# k210.net
KiCad netlist of a schematic drawn in Altium Designer
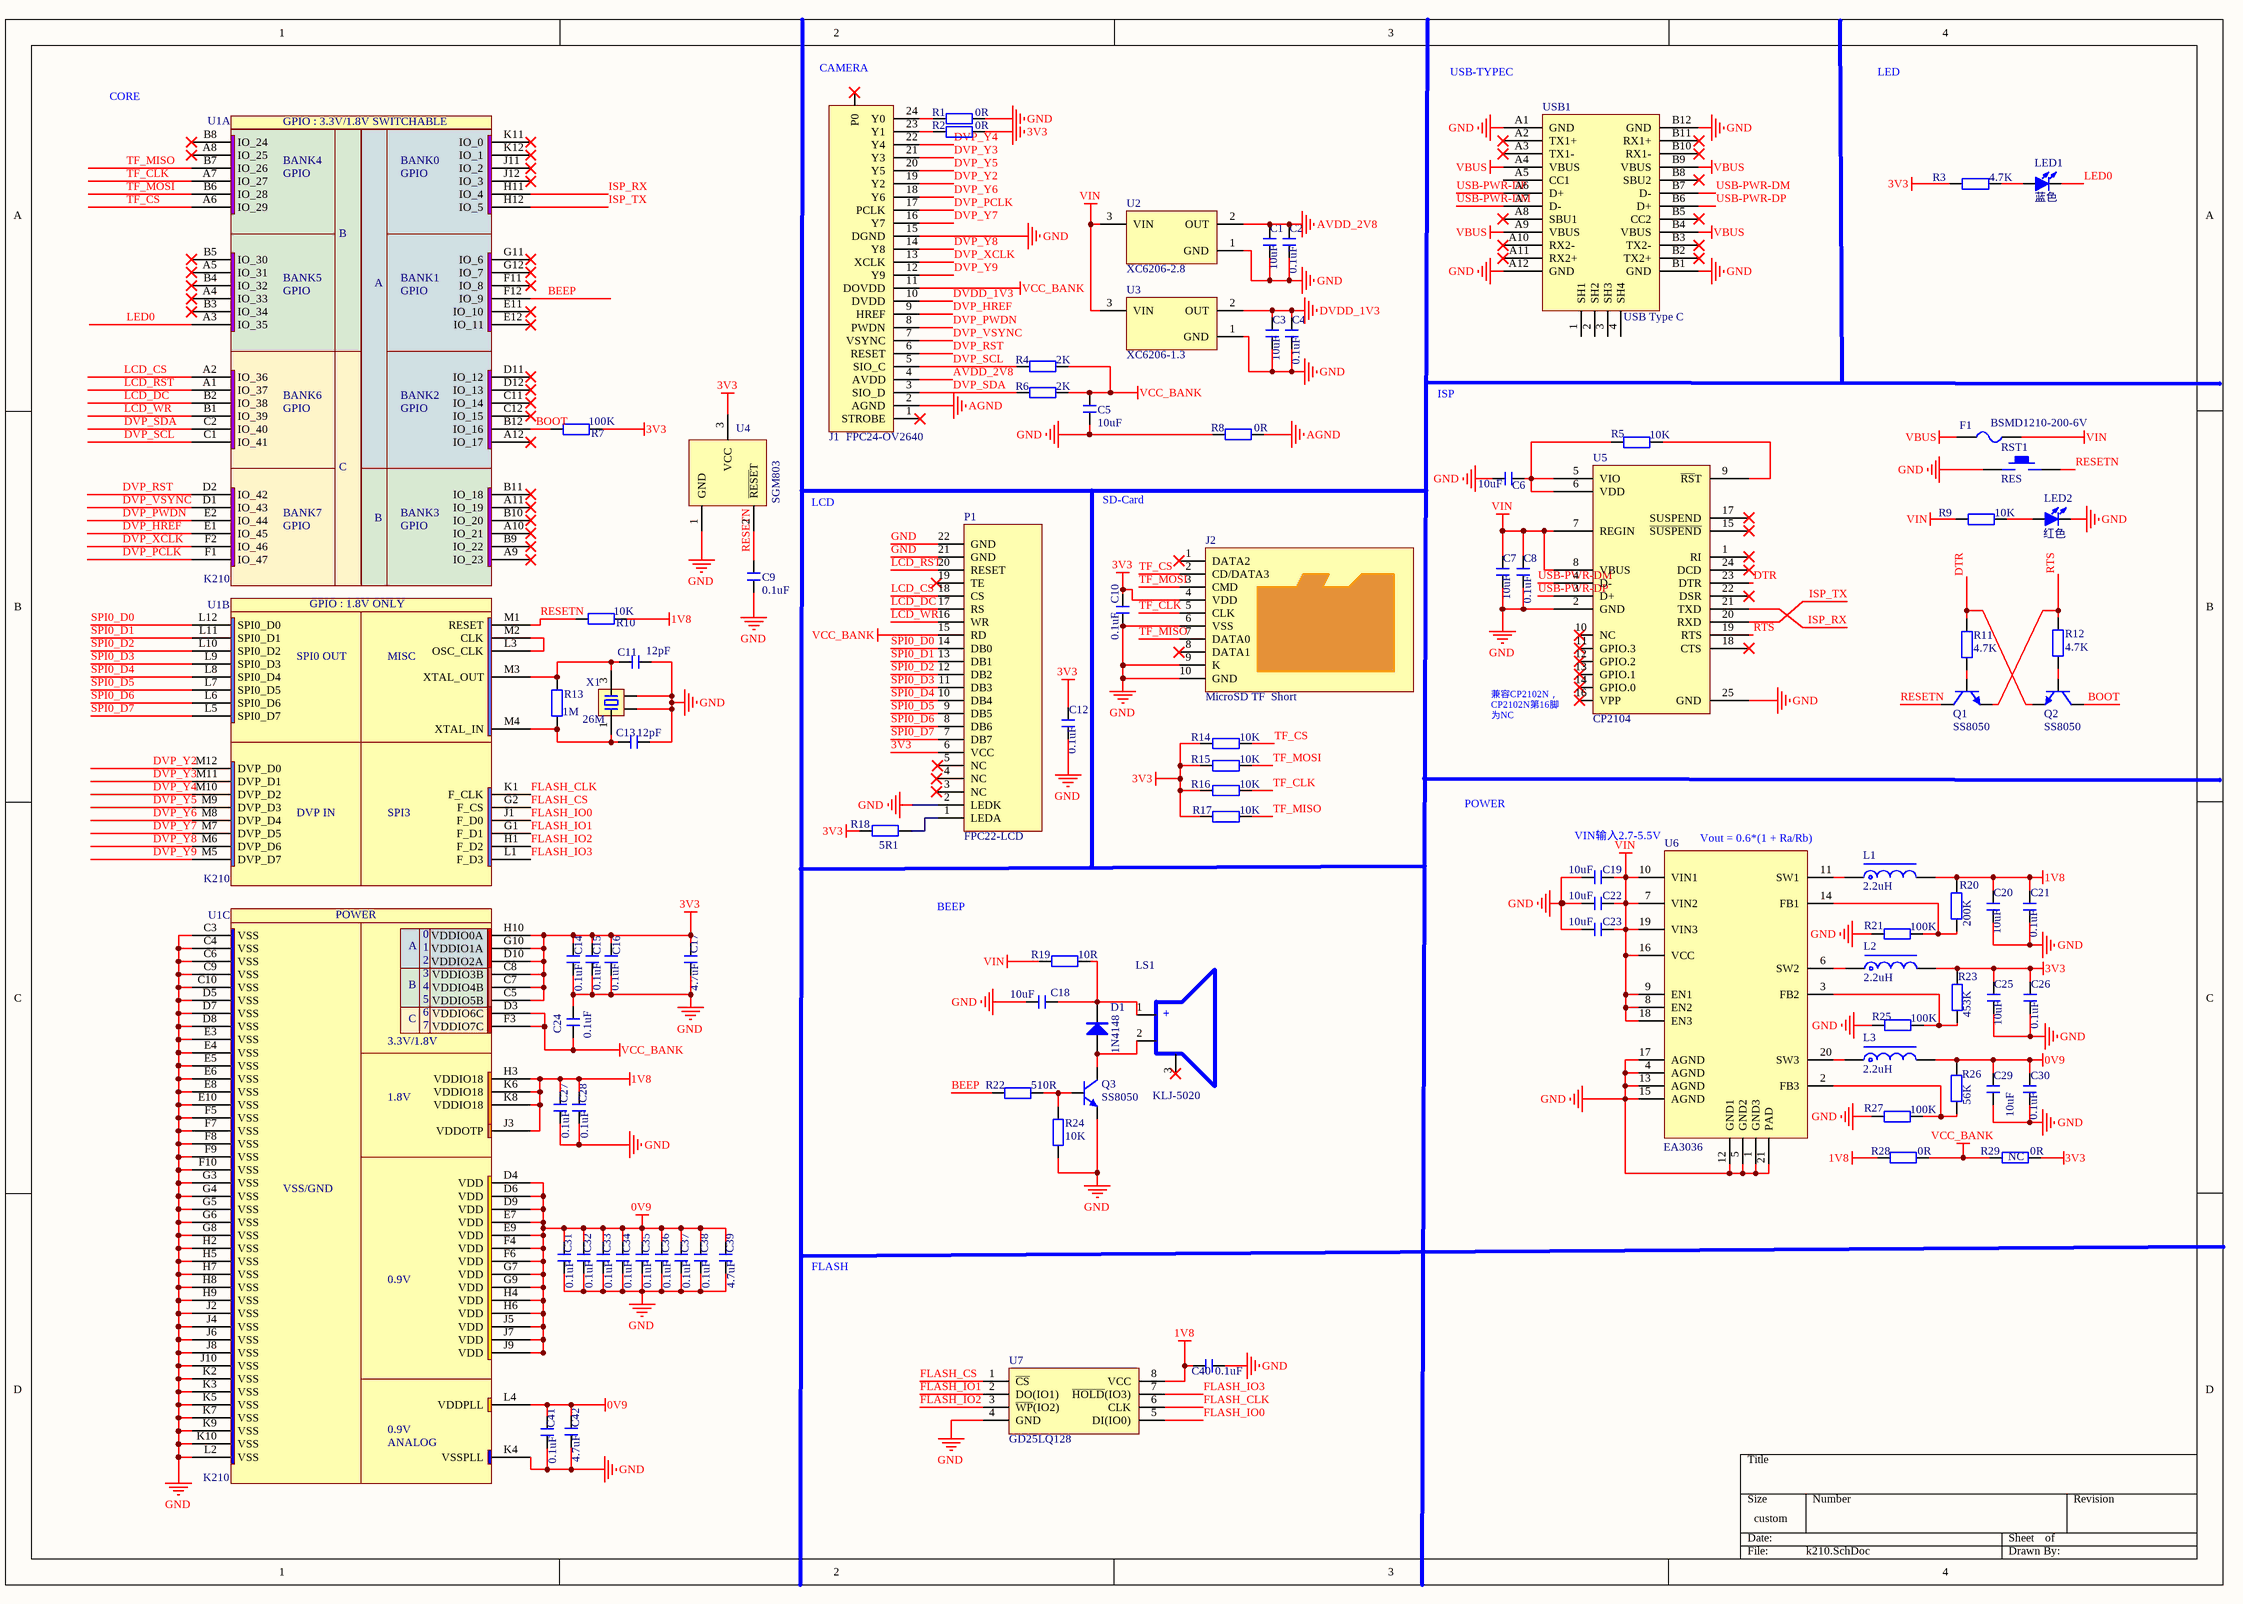
[diagram p0: k210.SchDoc]

(export (version "E")
  (design (tool "Eeschema 10.0.6"))
  (components
    (comp (ref "C1")
      (value "10uF")
      (footprint "C 0402_M")
      (description "贴片电容")
      (libsource (lib "0.1 - 电阻-电容-电感") (part "C"))
    )
    (comp (ref "C2")
      (value "0.1uF")
      (footprint "C 0402_M")
      (description "贴片电容")
      (libsource (lib "0.1 - 电阻-电容-电感") (part "C"))
    )
    (comp (ref "C3")
      (value "10uF")
      (footprint "C 0402_M")
      (description "贴片电容")
      (libsource (lib "0.1 - 电阻-电容-电感") (part "C"))
    )
    (comp (ref "C4")
      (value "0.1uF")
      (footprint "C 0402_M")
      (description "贴片电容")
      (libsource (lib "0.1 - 电阻-电容-电感") (part "C"))
    )
    (comp (ref "C5")
      (value "10uF")
      (footprint "C 0402_M")
      (description "贴片电容")
      (libsource (lib "0.1 - 电阻-电容-电感") (part "C"))
    )
    (comp (ref "C6")
      (value "10uF")
      (footprint "C 0402_M")
      (description "贴片电容")
      (libsource (lib "0.1 - 电阻-电容-电感") (part "C"))
    )
    (comp (ref "C7")
      (value "10uF")
      (footprint "C 0402_M")
      (description "贴片电容")
      (libsource (lib "0.1 - 电阻-电容-电感") (part "C"))
    )
    (comp (ref "C8")
      (value "0.1uF")
      (footprint "C 0402_M")
      (description "贴片电容")
      (libsource (lib "0.1 - 电阻-电容-电感") (part "C"))
    )
    (comp (ref "C9")
      (value "0.1uF")
      (footprint "C 0402_M")
      (description "贴片电容")
      (libsource (lib "0.1 - 电阻-电容-电感") (part "C"))
    )
    (comp (ref "C10")
      (value "0.1uF")
      (footprint "C 0402_M")
      (description "贴片电容")
      (libsource (lib "0.1 - 电阻-电容-电感") (part "C"))
    )
    (comp (ref "C11")
      (value "12pF")
      (footprint "C 0402_M")
      (description "贴片电容")
      (libsource (lib "0.1 - 电阻-电容-电感") (part "C"))
    )
    (comp (ref "C12")
      (value "0.1uF")
      (footprint "C 0402_M")
      (description "贴片电容")
      (libsource (lib "0.1 - 电阻-电容-电感") (part "C"))
    )
    (comp (ref "C13")
      (value "12pF")
      (footprint "C 0402_M")
      (description "贴片电容")
      (libsource (lib "0.1 - 电阻-电容-电感") (part "C"))
    )
    (comp (ref "C14")
      (value "0.1uF")
      (footprint "C 0402_M")
      (description "贴片电容")
      (libsource (lib "0.1 - 电阻-电容-电感") (part "C"))
    )
    (comp (ref "C15")
      (value "0.1uF")
      (footprint "C 0402_M")
      (description "贴片电容")
      (libsource (lib "0.1 - 电阻-电容-电感") (part "C"))
    )
    (comp (ref "C16")
      (value "0.1uF")
      (footprint "C 0402_M")
      (description "贴片电容")
      (libsource (lib "0.1 - 电阻-电容-电感") (part "C"))
    )
    (comp (ref "C17")
      (value "4.7uF")
      (footprint "C 0402_M")
      (description "贴片电容")
      (libsource (lib "0.1 - 电阻-电容-电感") (part "C"))
    )
    (comp (ref "C18")
      (value "10uF")
      (footprint "C 0402_M")
      (description "贴片电容")
      (libsource (lib "0.1 - 电阻-电容-电感") (part "C"))
    )
    (comp (ref "C19")
      (value "10uF")
      (footprint "C 0402_M")
      (description "贴片电容")
      (libsource (lib "0.1 - 电阻-电容-电感") (part "C"))
    )
    (comp (ref "C20")
      (value "10uF")
      (footprint "C 0402_M")
      (description "贴片电容")
      (libsource (lib "0.1 - 电阻-电容-电感") (part "C"))
    )
    (comp (ref "C21")
      (value "0.1uF")
      (footprint "C 0402_M")
      (description "贴片电容")
      (libsource (lib "0.1 - 电阻-电容-电感") (part "C"))
    )
    (comp (ref "C22")
      (value "10uF")
      (footprint "C 0402_M")
      (description "贴片电容")
      (libsource (lib "0.1 - 电阻-电容-电感") (part "C"))
    )
    (comp (ref "C23")
      (value "10uF")
      (footprint "C 0402_M")
      (description "贴片电容")
      (libsource (lib "0.1 - 电阻-电容-电感") (part "C"))
    )
    (comp (ref "C24")
      (value "0.1uF")
      (footprint "C 0402_M")
      (description "贴片电容")
      (libsource (lib "0.1 - 电阻-电容-电感") (part "C"))
    )
    (comp (ref "C25")
      (value "10uF")
      (footprint "C 0402_M")
      (description "贴片电容")
      (libsource (lib "0.1 - 电阻-电容-电感") (part "C"))
    )
    (comp (ref "C26")
      (value "0.1uF")
      (footprint "C 0402_M")
      (description "贴片电容")
      (libsource (lib "0.1 - 电阻-电容-电感") (part "C"))
    )
    (comp (ref "C27")
      (value "0.1uF")
      (footprint "C 0402_M")
      (description "贴片电容")
      (libsource (lib "0.1 - 电阻-电容-电感") (part "C"))
    )
    (comp (ref "C28")
      (value "0.1uF")
      (footprint "C 0402_M")
      (description "贴片电容")
      (libsource (lib "0.1 - 电阻-电容-电感") (part "C"))
    )
    (comp (ref "C29")
      (value "10uF")
      (footprint "C 0402_M")
      (description "贴片电容")
      (libsource (lib "0.1 - 电阻-电容-电感") (part "C"))
    )
    (comp (ref "C30")
      (value "0.1uF")
      (footprint "C 0402_M")
      (description "贴片电容")
      (libsource (lib "0.1 - 电阻-电容-电感") (part "C"))
    )
    (comp (ref "C31")
      (value "0.1uF")
      (footprint "C 0402_M")
      (description "贴片电容")
      (libsource (lib "0.1 - 电阻-电容-电感") (part "C"))
    )
    (comp (ref "C32")
      (value "0.1uF")
      (footprint "C 0402_M")
      (description "贴片电容")
      (libsource (lib "0.1 - 电阻-电容-电感") (part "C"))
    )
    (comp (ref "C33")
      (value "0.1uF")
      (footprint "C 0402_M")
      (description "贴片电容")
      (libsource (lib "0.1 - 电阻-电容-电感") (part "C"))
    )
    (comp (ref "C34")
      (value "0.1uF")
      (footprint "C 0402_M")
      (description "贴片电容")
      (libsource (lib "0.1 - 电阻-电容-电感") (part "C"))
    )
    (comp (ref "C35")
      (value "0.1uF")
      (footprint "C 0402_M")
      (description "贴片电容")
      (libsource (lib "0.1 - 电阻-电容-电感") (part "C"))
    )
    (comp (ref "C36")
      (value "0.1uF")
      (footprint "C 0402_M")
      (description "贴片电容")
      (libsource (lib "0.1 - 电阻-电容-电感") (part "C"))
    )
    (comp (ref "C37")
      (value "0.1uF")
      (footprint "C 0402_M")
      (description "贴片电容")
      (libsource (lib "0.1 - 电阻-电容-电感") (part "C"))
    )
    (comp (ref "C38")
      (value "0.1uF")
      (footprint "C 0402_M")
      (description "贴片电容")
      (libsource (lib "0.1 - 电阻-电容-电感") (part "C"))
    )
    (comp (ref "C39")
      (value "4.7uF")
      (footprint "C 0402_M")
      (description "贴片电容")
      (libsource (lib "0.1 - 电阻-电容-电感") (part "C"))
    )
    (comp (ref "C40")
      (value "0.1uF")
      (footprint "C 0402_M")
      (description "贴片电容")
      (libsource (lib "0.1 - 电阻-电容-电感") (part "C"))
    )
    (comp (ref "C41")
      (value "0.1uF")
      (footprint "C 0402_M")
      (description "贴片电容")
      (libsource (lib "0.1 - 电阻-电容-电感") (part "C"))
    )
    (comp (ref "C42")
      (value "4.7uF")
      (footprint "C 0402_M")
      (description "贴片电容")
      (libsource (lib "0.1 - 电阻-电容-电感") (part "C"))
    )
    (comp (ref "D1")
      (value "1N4148")
      (footprint "SOD-323")
      (description "开关二极管")
      (libsource (lib "0.2 -  二极管-整流桥") (part "1N4148"))
    )
    (comp (ref "F1")
      (value "BSMD1210-200-6V")
      (footprint "FU 1210")
      (description "贴片保险丝")
      (libsource (lib "2.0 - 保险丝-晶振-光耦") (part "FU"))
    )
    (comp (ref "J1")
      (value "FPC24-OV2640")
      (footprint "FPC0.5 2H-WS-24P")
      (description "Header, 24-Pin")
      (fields (field (name "PUBLISHER") "Altium Limited"))
      (libsource (lib "Vowstar_MCU") (part "OV5640"))
    )
    (comp (ref "J2")
      (value "MicroSD TF  Short")
      (footprint "TF-SOCKET - short")
      (description "TF卡座")
      (libsource (lib "0.8 - 网口-音频插座") (part "TF_Card"))
    )
    (comp (ref "L1")
      (value "2.2uH")
      (footprint "NR2520")
      (description "NR磁胶电感")
      (libsource (lib "0.1 - 电阻-电容-电感") (part "L-NR"))
    )
    (comp (ref "L2")
      (value "2.2uH")
      (footprint "NR2520")
      (description "NR磁胶电感")
      (libsource (lib "0.1 - 电阻-电容-电感") (part "L-NR"))
    )
    (comp (ref "L3")
      (value "2.2uH")
      (footprint "NR2520")
      (description "NR磁胶电感")
      (libsource (lib "0.1 - 电阻-电容-电感") (part "L-NR"))
    )
    (comp (ref "LED1")
      (value "蓝色")
      (footprint "LED 0805G")
      (description "贴片LED")
      (libsource (lib "0.3 - LED发光二极管") (part "LED-SMD"))
    )
    (comp (ref "LED2")
      (value "红色")
      (footprint "LED 0805G")
      (description "贴片LED")
      (libsource (lib "0.3 - LED发光二极管") (part "LED-SMD"))
    )
    (comp (ref "LS1")
      (value "KLJ-5020")
      (footprint "BUZ-SMD_4P-L5.0-W5.0-P3.80-TL")
      (description "蜂鸣器")
      (libsource (lib "mx_pcb_library") (part "KLJ-5020"))
    )
    (comp (ref "P1")
      (value "FPC22-LCD")
      (footprint "FPC0.5 2H-WS-22P")
      (libsource (lib "CanMV-K210") (part "FPC22_new"))
    )
    (comp (ref "Q1")
      (value "SS8050")
      (footprint "SOT23-3N")
      (description "高频放大-NPN型")
      (libsource (lib "0.4 - 三极管") (part "8050-SMD"))
    )
    (comp (ref "Q2")
      (value "SS8050")
      (footprint "SOT23-3N")
      (description "高频放大-NPN型")
      (libsource (lib "0.4 - 三极管") (part "8050-SMD"))
    )
    (comp (ref "Q3")
      (value "SS8050")
      (footprint "SOT23-3N")
      (description "高频放大-NPN型")
      (libsource (lib "0.4 - 三极管") (part "8050-SMD"))
    )
    (comp (ref "R1")
      (value "0R")
      (footprint "R 0402_M")
      (description "贴片电阻")
      (libsource (lib "0.1 - 电阻-电容-电感") (part "R"))
    )
    (comp (ref "R2")
      (value "0R")
      (footprint "R 0402_M")
      (description "贴片电阻")
      (libsource (lib "0.1 - 电阻-电容-电感") (part "R"))
    )
    (comp (ref "R3")
      (value "4.7K")
      (footprint "R 0402_M")
      (description "贴片电阻")
      (libsource (lib "0.1 - 电阻-电容-电感") (part "R"))
    )
    (comp (ref "R4")
      (value "2K")
      (footprint "R 0402_M")
      (description "贴片电阻")
      (libsource (lib "0.1 - 电阻-电容-电感") (part "R"))
    )
    (comp (ref "R5")
      (value "10K")
      (footprint "R 0402_M")
      (description "贴片电阻")
      (libsource (lib "0.1 - 电阻-电容-电感") (part "R"))
    )
    (comp (ref "R6")
      (value "2K")
      (footprint "R 0402_M")
      (description "贴片电阻")
      (libsource (lib "0.1 - 电阻-电容-电感") (part "R"))
    )
    (comp (ref "R7")
      (value "100K")
      (footprint "R 0402_M")
      (description "贴片电阻")
      (libsource (lib "0.1 - 电阻-电容-电感") (part "R"))
    )
    (comp (ref "R8")
      (value "0R")
      (footprint "R 0402_M")
      (description "贴片电阻")
      (libsource (lib "0.1 - 电阻-电容-电感") (part "R"))
    )
    (comp (ref "R9")
      (value "10K")
      (footprint "R 0402_M")
      (description "贴片电阻")
      (libsource (lib "0.1 - 电阻-电容-电感") (part "R"))
    )
    (comp (ref "R10")
      (value "10K")
      (footprint "R 0402_M")
      (description "贴片电阻")
      (libsource (lib "0.1 - 电阻-电容-电感") (part "R"))
    )
    (comp (ref "R11")
      (value "4.7K")
      (footprint "R 0402_M")
      (description "贴片电阻")
      (libsource (lib "0.1 - 电阻-电容-电感") (part "R"))
    )
    (comp (ref "R12")
      (value "4.7K")
      (footprint "R 0402_M")
      (description "贴片电阻")
      (libsource (lib "0.1 - 电阻-电容-电感") (part "R"))
    )
    (comp (ref "R13")
      (value "1M")
      (footprint "R 0402_M")
      (description "贴片电阻")
      (libsource (lib "0.1 - 电阻-电容-电感") (part "R"))
    )
    (comp (ref "R14")
      (value "10K")
      (footprint "R 0402_M")
      (description "贴片电阻")
      (libsource (lib "0.1 - 电阻-电容-电感") (part "R"))
    )
    (comp (ref "R15")
      (value "10K")
      (footprint "R 0402_M")
      (description "贴片电阻")
      (libsource (lib "0.1 - 电阻-电容-电感") (part "R"))
    )
    (comp (ref "R16")
      (value "10K")
      (footprint "R 0402_M")
      (description "贴片电阻")
      (libsource (lib "0.1 - 电阻-电容-电感") (part "R"))
    )
    (comp (ref "R17")
      (value "10K")
      (footprint "R 0402_M")
      (description "贴片电阻")
      (libsource (lib "0.1 - 电阻-电容-电感") (part "R"))
    )
    (comp (ref "R18")
      (value "5R1")
      (footprint "R 0402_M")
      (description "贴片电阻")
      (libsource (lib "0.1 - 电阻-电容-电感") (part "R"))
    )
    (comp (ref "R19")
      (value "10R")
      (footprint "R 0402_M")
      (description "贴片电阻")
      (libsource (lib "0.1 - 电阻-电容-电感") (part "R"))
    )
    (comp (ref "R20")
      (value "200K")
      (footprint "R 0402_M")
      (description "贴片电阻")
      (libsource (lib "0.1 - 电阻-电容-电感") (part "R"))
    )
    (comp (ref "R21")
      (value "100K")
      (footprint "R 0402_M")
      (description "贴片电阻")
      (libsource (lib "0.1 - 电阻-电容-电感") (part "R"))
    )
    (comp (ref "R22")
      (value "510R")
      (footprint "R 0402_M")
      (description "贴片电阻")
      (libsource (lib "0.1 - 电阻-电容-电感") (part "R"))
    )
    (comp (ref "R23")
      (value "453K")
      (footprint "R 0402_M")
      (description "贴片电阻")
      (libsource (lib "0.1 - 电阻-电容-电感") (part "R"))
    )
    (comp (ref "R24")
      (value "10K")
      (footprint "R 0402_M")
      (description "贴片电阻")
      (libsource (lib "0.1 - 电阻-电容-电感") (part "R"))
    )
    (comp (ref "R25")
      (value "100K")
      (footprint "R 0402_M")
      (description "贴片电阻")
      (libsource (lib "0.1 - 电阻-电容-电感") (part "R"))
    )
    (comp (ref "R26")
      (value "56K")
      (footprint "R 0402_M")
      (description "贴片电阻")
      (libsource (lib "0.1 - 电阻-电容-电感") (part "R"))
    )
    (comp (ref "R27")
      (value "100K")
      (footprint "R 0402_M")
      (description "贴片电阻")
      (libsource (lib "0.1 - 电阻-电容-电感") (part "R"))
    )
    (comp (ref "R28")
      (value "0R")
      (footprint "R 0402_M")
      (description "贴片电阻")
      (libsource (lib "0.1 - 电阻-电容-电感") (part "R"))
    )
    (comp (ref "R29")
      (value "0R")
      (footprint "R 0402_M")
      (description "贴片电阻")
      (libsource (lib "0.1 - 电阻-电容-电感") (part "R"))
    )
    (comp (ref "RST1")
      (value "RES")
      (footprint "CanMV-K210:SMD-3.2*4.2")
      (libsource (lib "mx_pcb_library") (part "KEY_M"))
    )
    (comp (ref "U1")
      (value "K210")
      (footprint "BGA144C65P12X12_800X800X95")
      (description "Canaan Kendryte K210 AI SoC")
      (libsource (lib "Vowstar_MCU") (part "K210"))
    )
    (comp (ref "U2")
      (value "XC6206-2.8")
      (footprint "CanMV-K210:SOT23-3N")
      (description "SOT-23,XC6206P332MR,MAX8V,100mA")
      (libsource (lib "1.1 - 电源类芯片") (part "XC6206-3.3"))
    )
    (comp (ref "U3")
      (value "XC6206-1.3")
      (footprint "CanMV-K210:SOT23-3N")
      (description "SOT-23,XC6206P332MR,MAX8V,100mA")
      (libsource (lib "1.1 - 电源类芯片") (part "XC6206-3.3"))
    )
    (comp (ref "U4")
      (value "SGM803")
      (footprint "CanMV-K210:SOT23-3N")
      (libsource (lib "Vowstar_MCU") (part "SGM803"))
    )
    (comp (ref "U5")
      (value "CP2104")
      (footprint "QFN-24_L4.0-W4.0-P0.50-BL-EP2.8")
      (libsource (lib "Vowstar_MCU") (part "CP2104"))
    )
    (comp (ref "U6")
      (value "EA3036")
      (footprint "QFN20_40P300X300X80_HS-21N")
      (libsource (lib "Vowstar_MCU") (part "EA3036"))
    )
    (comp (ref "U7")
      (value "GD25LQ128")
      (footprint "WSON-8_L8.0-W6.10-P1.27-BL-EP")
      (description "WSON-8")
      (libsource (lib "Vowstar_MCU") (part "GD25LQ128"))
    )
    (comp (ref "USB1")
      (value "USB Type C")
      (footprint "Type-C-TOP")
      (libsource (lib "Vowstar_MCU") (part "USB_Type-C"))
    )
    (comp (ref "X1")
      (value "26M")
      (footprint "OSC 3225-4P")
      (description "4脚无源晶振")
      (libsource (lib "2.0 - 保险丝-晶振-光耦") (part "XTAL-4P"))
    )
  )
  (nets
    (net (code "1") (name "/BEEP") (class "Default")
      (node (ref "R22") (pin "1") (pinfunction "1_1") (pintype "passive"))
      (node (ref "U1") (pin "F12") (pinfunction "IO_9_F12") (pintype "passive"))
    )
    (net (code "2") (name "/BOOT") (class "Default")
      (node (ref "Q2") (pin "3") (pinfunction "C_3") (pintype "passive"))
      (node (ref "R7") (pin "1") (pinfunction "1_1") (pintype "passive"))
      (node (ref "U1") (pin "B12") (pinfunction "IO_16_B12") (pintype "passive"))
    )
    (net (code "3") (name "/DTR") (class "Default")
      (node (ref "Q2") (pin "2") (pinfunction "E_2") (pintype "passive"))
      (node (ref "R11") (pin "1") (pinfunction "1_1") (pintype "passive"))
      (node (ref "U5") (pin "23") (pinfunction "DTR_23") (pintype "passive"))
    )
    (net (code "4") (name "/DVP_HREF") (class "Default")
      (node (ref "J1") (pin "9") (pinfunction "HREF_9") (pintype "passive"))
      (node (ref "U1") (pin "E1") (pinfunction "IO_45_E1") (pintype "passive"))
    )
    (net (code "5") (name "/DVP_PCLK") (class "Default")
      (node (ref "J1") (pin "17") (pinfunction "PCLK_17") (pintype "passive"))
      (node (ref "U1") (pin "F1") (pinfunction "IO_47_F1") (pintype "passive"))
    )
    (net (code "6") (name "/DVP_PWDN") (class "Default")
      (node (ref "J1") (pin "8") (pinfunction "PWDN_8") (pintype "passive"))
      (node (ref "U1") (pin "E2") (pinfunction "IO_44_E2") (pintype "passive"))
    )
    (net (code "7") (name "/DVP_RST") (class "Default")
      (node (ref "J1") (pin "6") (pinfunction "RESET_6") (pintype "passive"))
      (node (ref "U1") (pin "D2") (pinfunction "IO_42_D2") (pintype "passive"))
    )
    (net (code "8") (name "/DVP_SCL") (class "Default")
      (node (ref "J1") (pin "5") (pinfunction "SIO_C_5") (pintype "passive"))
      (node (ref "R4") (pin "1") (pinfunction "1_1") (pintype "passive"))
      (node (ref "U1") (pin "C1") (pinfunction "IO_41_C1") (pintype "passive"))
    )
    (net (code "9") (name "/DVP_SDA") (class "Default")
      (node (ref "J1") (pin "3") (pinfunction "SIO_D_3") (pintype "passive"))
      (node (ref "R6") (pin "1") (pinfunction "1_1") (pintype "passive"))
      (node (ref "U1") (pin "C2") (pinfunction "IO_40_C2") (pintype "passive"))
    )
    (net (code "10") (name "/DVP_VSYNC") (class "Default")
      (node (ref "J1") (pin "7") (pinfunction "VSYNC_7") (pintype "passive"))
      (node (ref "U1") (pin "D1") (pinfunction "IO_43_D1") (pintype "passive"))
    )
    (net (code "11") (name "/DVP_XCLK") (class "Default")
      (node (ref "J1") (pin "13") (pinfunction "XCLK_13") (pintype "passive"))
      (node (ref "U1") (pin "F2") (pinfunction "IO_46_F2") (pintype "passive"))
    )
    (net (code "12") (name "/DVP_Y2") (class "Default")
      (node (ref "J1") (pin "19") (pinfunction "Y2_19") (pintype "passive"))
      (node (ref "U1") (pin "M12") (pinfunction "DVP_D0_M12") (pintype "passive"))
    )
    (net (code "13") (name "/DVP_Y3") (class "Default")
      (node (ref "J1") (pin "21") (pinfunction "Y3_21") (pintype "passive"))
      (node (ref "U1") (pin "M11") (pinfunction "DVP_D1_M11") (pintype "passive"))
    )
    (net (code "14") (name "/DVP_Y4") (class "Default")
      (node (ref "J1") (pin "22") (pinfunction "Y4_22") (pintype "passive"))
      (node (ref "U1") (pin "M10") (pinfunction "DVP_D2_M10") (pintype "passive"))
    )
    (net (code "15") (name "/DVP_Y5") (class "Default")
      (node (ref "J1") (pin "20") (pinfunction "Y5_20") (pintype "passive"))
      (node (ref "U1") (pin "M9") (pinfunction "DVP_D3_M9") (pintype "passive"))
    )
    (net (code "16") (name "/DVP_Y6") (class "Default")
      (node (ref "J1") (pin "18") (pinfunction "Y6_18") (pintype "passive"))
      (node (ref "U1") (pin "M8") (pinfunction "DVP_D4_M8") (pintype "passive"))
    )
    (net (code "17") (name "/DVP_Y7") (class "Default")
      (node (ref "J1") (pin "16") (pinfunction "Y7_16") (pintype "passive"))
      (node (ref "U1") (pin "M7") (pinfunction "DVP_D5_M7") (pintype "passive"))
    )
    (net (code "18") (name "/DVP_Y8") (class "Default")
      (node (ref "J1") (pin "14") (pinfunction "Y8_14") (pintype "passive"))
      (node (ref "U1") (pin "M6") (pinfunction "DVP_D6_M6") (pintype "passive"))
    )
    (net (code "19") (name "/DVP_Y9") (class "Default")
      (node (ref "J1") (pin "12") (pinfunction "Y9_12") (pintype "passive"))
      (node (ref "U1") (pin "M5") (pinfunction "DVP_D7_M5") (pintype "passive"))
    )
    (net (code "20") (name "/FLASH_CLK") (class "Default")
      (node (ref "U1") (pin "K1") (pinfunction "F_CLK_K1") (pintype "passive"))
      (node (ref "U7") (pin "6") (pinfunction "CLK_6") (pintype "passive"))
    )
    (net (code "21") (name "/FLASH_CS") (class "Default")
      (node (ref "U1") (pin "G2") (pinfunction "F_CS_G2") (pintype "passive"))
      (node (ref "U7") (pin "1") (pinfunction "~{CS}_1") (pintype "passive"))
    )
    (net (code "22") (name "/FLASH_IO0") (class "Default")
      (node (ref "U1") (pin "J1") (pinfunction "F_D0_J1") (pintype "passive"))
      (node (ref "U7") (pin "5") (pinfunction "DI(IO0)_5") (pintype "passive"))
    )
    (net (code "23") (name "/FLASH_IO1") (class "Default")
      (node (ref "U1") (pin "G1") (pinfunction "F_D1_G1") (pintype "passive"))
      (node (ref "U7") (pin "2") (pinfunction "DO(IO1)_2") (pintype "passive"))
    )
    (net (code "24") (name "/FLASH_IO2") (class "Default")
      (node (ref "U1") (pin "H1") (pinfunction "F_D2_H1") (pintype "passive"))
      (node (ref "U7") (pin "3") (pinfunction "~{WP}(IO2)_3") (pintype "passive"))
    )
    (net (code "25") (name "/FLASH_IO3") (class "Default")
      (node (ref "U1") (pin "L1") (pinfunction "F_D3_L1") (pintype "passive"))
      (node (ref "U7") (pin "7") (pinfunction "~{HOLD}(IO3)_7") (pintype "passive"))
    )
    (net (code "26") (name "/ISP_RX") (class "Default")
      (node (ref "U1") (pin "H11") (pinfunction "IO_4_H11") (pintype "passive"))
      (node (ref "U5") (pin "21") (pinfunction "TXD_21") (pintype "passive"))
    )
    (net (code "27") (name "/ISP_TX") (class "Default")
      (node (ref "U1") (pin "H12") (pinfunction "IO_5_H12") (pintype "passive"))
      (node (ref "U5") (pin "20") (pinfunction "RXD_20") (pintype "passive"))
    )
    (net (code "28") (name "/LCD_CS") (class "Default")
      (node (ref "P1") (pin "18") (pinfunction "CS_18") (pintype "passive"))
      (node (ref "U1") (pin "A2") (pinfunction "IO_36_A2") (pintype "passive"))
    )
    (net (code "29") (name "/LCD_DC") (class "Default")
      (node (ref "P1") (pin "17") (pinfunction "RS_17") (pintype "passive"))
      (node (ref "U1") (pin "B2") (pinfunction "IO_38_B2") (pintype "passive"))
    )
    (net (code "30") (name "/LCD_RST") (class "Default")
      (node (ref "P1") (pin "20") (pinfunction "RESET_20") (pintype "passive"))
      (node (ref "U1") (pin "A1") (pinfunction "IO_37_A1") (pintype "passive"))
    )
    (net (code "31") (name "/LCD_WR") (class "Default")
      (node (ref "P1") (pin "16") (pinfunction "WR_16") (pintype "passive"))
      (node (ref "U1") (pin "B1") (pinfunction "IO_39_B1") (pintype "passive"))
    )
    (net (code "32") (name "/LED0") (class "Default")
      (node (ref "LED1") (pin "2") (pinfunction "K_2") (pintype "passive"))
      (node (ref "U1") (pin "A3") (pinfunction "IO_35_A3") (pintype "passive"))
    )
    (net (code "33") (name "/RESETN") (class "Default")
      (node (ref "C9") (pin "1") (pinfunction "1_1") (pintype "passive"))
      (node (ref "Q1") (pin "3") (pinfunction "C_3") (pintype "passive"))
      (node (ref "R10") (pin "1") (pinfunction "1_1") (pintype "passive"))
      (node (ref "RST1") (pin "2") (pinfunction "2_2") (pintype "passive"))
      (node (ref "U1") (pin "M1") (pinfunction "RESET_M1") (pintype "passive"))
      (node (ref "U4") (pin "2") (pinfunction "~{RESE}T_2") (pintype "passive"))
    )
    (net (code "34") (name "/RTS") (class "Default")
      (node (ref "Q1") (pin "2") (pinfunction "E_2") (pintype "passive"))
      (node (ref "R12") (pin "1") (pinfunction "1_1") (pintype "passive"))
      (node (ref "U5") (pin "19") (pinfunction "RTS_19") (pintype "passive"))
    )
    (net (code "35") (name "/SPI0_D0") (class "Default")
      (node (ref "P1") (pin "14") (pinfunction "DB0_14") (pintype "passive"))
      (node (ref "U1") (pin "L12") (pinfunction "SPI0_D0_L12") (pintype "passive"))
    )
    (net (code "36") (name "/SPI0_D1") (class "Default")
      (node (ref "P1") (pin "13") (pinfunction "DB1_13") (pintype "passive"))
      (node (ref "U1") (pin "L11") (pinfunction "SPI0_D1_L11") (pintype "passive"))
    )
    (net (code "37") (name "/SPI0_D2") (class "Default")
      (node (ref "P1") (pin "12") (pinfunction "DB2_12") (pintype "passive"))
      (node (ref "U1") (pin "L10") (pinfunction "SPI0_D2_L10") (pintype "passive"))
    )
    (net (code "38") (name "/SPI0_D3") (class "Default")
      (node (ref "P1") (pin "11") (pinfunction "DB3_11") (pintype "passive"))
      (node (ref "U1") (pin "L9") (pinfunction "SPI0_D3_L9") (pintype "passive"))
    )
    (net (code "39") (name "/SPI0_D4") (class "Default")
      (node (ref "P1") (pin "10") (pinfunction "DB4_10") (pintype "passive"))
      (node (ref "U1") (pin "L8") (pinfunction "SPI0_D4_L8") (pintype "passive"))
    )
    (net (code "40") (name "/SPI0_D5") (class "Default")
      (node (ref "P1") (pin "9") (pinfunction "DB5_9") (pintype "passive"))
      (node (ref "U1") (pin "L7") (pinfunction "SPI0_D5_L7") (pintype "passive"))
    )
    (net (code "41") (name "/SPI0_D6") (class "Default")
      (node (ref "P1") (pin "8") (pinfunction "DB6_8") (pintype "passive"))
      (node (ref "U1") (pin "L6") (pinfunction "SPI0_D6_L6") (pintype "passive"))
    )
    (net (code "42") (name "/SPI0_D7") (class "Default")
      (node (ref "P1") (pin "7") (pinfunction "DB7_7") (pintype "passive"))
      (node (ref "U1") (pin "L5") (pinfunction "SPI0_D7_L5") (pintype "passive"))
    )
    (net (code "43") (name "/TF_CLK") (class "Default")
      (node (ref "J2") (pin "5") (pinfunction "CLK_5") (pintype "passive"))
      (node (ref "R16") (pin "2") (pinfunction "2_2") (pintype "passive"))
      (node (ref "U1") (pin "A7") (pinfunction "IO_27_A7") (pintype "passive"))
    )
    (net (code "44") (name "/TF_CS") (class "Default")
      (node (ref "J2") (pin "2") (pinfunction "CD/DATA3_2") (pintype "passive"))
      (node (ref "R14") (pin "2") (pinfunction "2_2") (pintype "passive"))
      (node (ref "U1") (pin "A6") (pinfunction "IO_29_A6") (pintype "passive"))
    )
    (net (code "45") (name "/TF_MISO") (class "Default")
      (node (ref "J2") (pin "7") (pinfunction "DATA0_7") (pintype "passive"))
      (node (ref "R17") (pin "2") (pinfunction "2_2") (pintype "passive"))
      (node (ref "U1") (pin "B7") (pinfunction "IO_26_B7") (pintype "passive"))
    )
    (net (code "46") (name "/TF_MOSI") (class "Default")
      (node (ref "J2") (pin "3") (pinfunction "CMD_3") (pintype "passive"))
      (node (ref "R15") (pin "2") (pinfunction "2_2") (pintype "passive"))
      (node (ref "U1") (pin "B6") (pinfunction "IO_28_B6") (pintype "passive"))
    )
    (net (code "47") (name "/USB-PWR-DM") (class "Default")
      (node (ref "U5") (pin "4") (pinfunction "D-_4") (pintype "passive"))
      (node (ref "USB1") (pin "A7") (pinfunction "D-_A7") (pintype "passive"))
      (node (ref "USB1") (pin "B7") (pinfunction "D-_B7") (pintype "passive"))
    )
    (net (code "48") (name "/USB-PWR-DP") (class "Default")
      (node (ref "U5") (pin "3") (pinfunction "D+_3") (pintype "passive"))
      (node (ref "USB1") (pin "A6") (pinfunction "D+_A6") (pintype "passive"))
      (node (ref "USB1") (pin "B6") (pinfunction "D+_B6") (pintype "passive"))
    )
    (net (code "49") (name "0V9") (class "Default")
      (node (ref "C29") (pin "2") (pinfunction "2_2") (pintype "passive"))
      (node (ref "C30") (pin "2") (pinfunction "2_2") (pintype "passive"))
      (node (ref "C31") (pin "1") (pinfunction "1_1") (pintype "passive"))
      (node (ref "C32") (pin "1") (pinfunction "1_1") (pintype "passive"))
      (node (ref "C33") (pin "1") (pinfunction "1_1") (pintype "passive"))
      (node (ref "C34") (pin "1") (pinfunction "1_1") (pintype "passive"))
      (node (ref "C35") (pin "1") (pinfunction "1_1") (pintype "passive"))
      (node (ref "C36") (pin "1") (pinfunction "1_1") (pintype "passive"))
      (node (ref "C37") (pin "1") (pinfunction "1_1") (pintype "passive"))
      (node (ref "C38") (pin "1") (pinfunction "1_1") (pintype "passive"))
      (node (ref "C39") (pin "1") (pinfunction "1_1") (pintype "passive"))
      (node (ref "C41") (pin "1") (pinfunction "1_1") (pintype "passive"))
      (node (ref "C42") (pin "1") (pinfunction "1_1") (pintype "passive"))
      (node (ref "L3") (pin "2") (pinfunction "2_2") (pintype "passive"))
      (node (ref "R26") (pin "2") (pinfunction "2_2") (pintype "passive"))
      (node (ref "U1") (pin "D4") (pinfunction "VDD_D4") (pintype "power_in"))
      (node (ref "U1") (pin "D6") (pinfunction "VDD_D6") (pintype "power_in"))
      (node (ref "U1") (pin "D9") (pinfunction "VDD_D9") (pintype "power_in"))
      (node (ref "U1") (pin "E7") (pinfunction "VDD_E7") (pintype "power_in"))
      (node (ref "U1") (pin "E9") (pinfunction "VDD_E9") (pintype "power_in"))
      (node (ref "U1") (pin "F4") (pinfunction "VDD_F4") (pintype "power_in"))
      (node (ref "U1") (pin "F6") (pinfunction "VDD_F6") (pintype "power_in"))
      (node (ref "U1") (pin "G7") (pinfunction "VDD_G7") (pintype "power_in"))
      (node (ref "U1") (pin "G9") (pinfunction "VDD_G9") (pintype "power_in"))
      (node (ref "U1") (pin "H4") (pinfunction "VDD_H4") (pintype "power_in"))
      (node (ref "U1") (pin "H6") (pinfunction "VDD_H6") (pintype "power_in"))
      (node (ref "U1") (pin "J5") (pinfunction "VDD_J5") (pintype "power_in"))
      (node (ref "U1") (pin "J7") (pinfunction "VDD_J7") (pintype "power_in"))
      (node (ref "U1") (pin "J9") (pinfunction "VDD_J9") (pintype "power_in"))
      (node (ref "U1") (pin "L4") (pinfunction "VDDPLL_L4") (pintype "power_in"))
    )
    (net (code "50") (name "1V8") (class "Default")
      (node (ref "C20") (pin "2") (pinfunction "2_2") (pintype "passive"))
      (node (ref "C21") (pin "2") (pinfunction "2_2") (pintype "passive"))
      (node (ref "C27") (pin "1") (pinfunction "1_1") (pintype "passive"))
      (node (ref "C28") (pin "1") (pinfunction "1_1") (pintype "passive"))
      (node (ref "C40") (pin "2") (pinfunction "2_2") (pintype "passive"))
      (node (ref "L1") (pin "2") (pinfunction "2_2") (pintype "passive"))
      (node (ref "R10") (pin "2") (pinfunction "2_2") (pintype "passive"))
      (node (ref "R20") (pin "2") (pinfunction "2_2") (pintype "passive"))
      (node (ref "R28") (pin "2") (pinfunction "2_2") (pintype "passive"))
      (node (ref "U1") (pin "H3") (pinfunction "VDDIO18_H3") (pintype "power_in"))
      (node (ref "U1") (pin "J3") (pinfunction "VDDOTP_J3") (pintype "power_in"))
      (node (ref "U1") (pin "K6") (pinfunction "VDDIO18_K6") (pintype "power_in"))
      (node (ref "U1") (pin "K8") (pinfunction "VDDIO18_K8") (pintype "power_in"))
      (node (ref "U7") (pin "8") (pinfunction "VCC_8") (pintype "passive"))
    )
    (net (code "51") (name "3V3") (class "Default")
      (node (ref "C10") (pin "1") (pinfunction "1_1") (pintype "passive"))
      (node (ref "C12") (pin "2") (pinfunction "2_2") (pintype "passive"))
      (node (ref "C14") (pin "2") (pinfunction "2_2") (pintype "passive"))
      (node (ref "C15") (pin "2") (pinfunction "2_2") (pintype "passive"))
      (node (ref "C16") (pin "2") (pinfunction "2_2") (pintype "passive"))
      (node (ref "C17") (pin "2") (pinfunction "2_2") (pintype "passive"))
      (node (ref "C25") (pin "2") (pinfunction "2_2") (pintype "passive"))
      (node (ref "C26") (pin "2") (pinfunction "2_2") (pintype "passive"))
      (node (ref "J2") (pin "4") (pinfunction "VDD_4") (pintype "passive"))
      (node (ref "L2") (pin "2") (pinfunction "2_2") (pintype "passive"))
      (node (ref "P1") (pin "6") (pinfunction "VCC_6") (pintype "passive"))
      (node (ref "R14") (pin "1") (pinfunction "1_1") (pintype "passive"))
      (node (ref "R15") (pin "1") (pinfunction "1_1") (pintype "passive"))
      (node (ref "R16") (pin "1") (pinfunction "1_1") (pintype "passive"))
      (node (ref "R17") (pin "1") (pinfunction "1_1") (pintype "passive"))
      (node (ref "R18") (pin "1") (pinfunction "1_1") (pintype "passive"))
      (node (ref "R2") (pin "2") (pinfunction "2_2") (pintype "passive"))
      (node (ref "R23") (pin "2") (pinfunction "2_2") (pintype "passive"))
      (node (ref "R29") (pin "1") (pinfunction "1_1") (pintype "passive"))
      (node (ref "R3") (pin "1") (pinfunction "1_1") (pintype "passive"))
      (node (ref "R7") (pin "2") (pinfunction "2_2") (pintype "passive"))
      (node (ref "U1") (pin "C5") (pinfunction "VDDIO5B_C5") (pintype "power_in"))
      (node (ref "U1") (pin "C7") (pinfunction "VDDIO4B_C7") (pintype "power_in"))
      (node (ref "U1") (pin "C8") (pinfunction "VDDIO3B_C8") (pintype "power_in"))
      (node (ref "U1") (pin "D10") (pinfunction "VDDIO2A_D10") (pintype "power_in"))
      (node (ref "U1") (pin "G10") (pinfunction "VDDIO1A_G10") (pintype "power_in"))
      (node (ref "U1") (pin "H10") (pinfunction "VDDIO0A_H10") (pintype "power_in"))
      (node (ref "U4") (pin "3") (pinfunction "VCC_3") (pintype "passive"))
    )
    (net (code "52") (name "AGND") (class "Default")
      (node (ref "J1") (pin "2") (pinfunction "AGND_2") (pintype "passive"))
      (node (ref "R8") (pin "2") (pinfunction "2_2") (pintype "passive"))
    )
    (net (code "53") (name "AVDD_2V8") (class "Default")
      (node (ref "C1") (pin "2") (pinfunction "2_2") (pintype "passive"))
      (node (ref "C2") (pin "2") (pinfunction "2_2") (pintype "passive"))
      (node (ref "J1") (pin "4") (pinfunction "AVDD_4") (pintype "passive"))
      (node (ref "U2") (pin "2") (pinfunction "OUT_2") (pintype "passive"))
    )
    (net (code "54") (name "DVDD_1V3") (class "Default")
      (node (ref "C3") (pin "2") (pinfunction "2_2") (pintype "passive"))
      (node (ref "C4") (pin "2") (pinfunction "2_2") (pintype "passive"))
      (node (ref "J1") (pin "10") (pinfunction "DVDD_10") (pintype "passive"))
      (node (ref "U3") (pin "2") (pinfunction "OUT_2") (pintype "passive"))
    )
    (net (code "55") (name "GND") (class "Default")
      (node (ref "C1") (pin "1") (pinfunction "1_1") (pintype "passive"))
      (node (ref "C10") (pin "2") (pinfunction "2_2") (pintype "passive"))
      (node (ref "C11") (pin "2") (pinfunction "2_2") (pintype "passive"))
      (node (ref "C12") (pin "1") (pinfunction "1_1") (pintype "passive"))
      (node (ref "C13") (pin "2") (pinfunction "2_2") (pintype "passive"))
      (node (ref "C14") (pin "1") (pinfunction "1_1") (pintype "passive"))
      (node (ref "C15") (pin "1") (pinfunction "1_1") (pintype "passive"))
      (node (ref "C16") (pin "1") (pinfunction "1_1") (pintype "passive"))
      (node (ref "C17") (pin "1") (pinfunction "1_1") (pintype "passive"))
      (node (ref "C18") (pin "1") (pinfunction "1_1") (pintype "passive"))
      (node (ref "C19") (pin "2") (pinfunction "2_2") (pintype "passive"))
      (node (ref "C2") (pin "1") (pinfunction "1_1") (pintype "passive"))
      (node (ref "C20") (pin "1") (pinfunction "1_1") (pintype "passive"))
      (node (ref "C21") (pin "1") (pinfunction "1_1") (pintype "passive"))
      (node (ref "C22") (pin "2") (pinfunction "2_2") (pintype "passive"))
      (node (ref "C23") (pin "2") (pinfunction "2_2") (pintype "passive"))
      (node (ref "C24") (pin "1") (pinfunction "1_1") (pintype "passive"))
      (node (ref "C25") (pin "1") (pinfunction "1_1") (pintype "passive"))
      (node (ref "C26") (pin "1") (pinfunction "1_1") (pintype "passive"))
      (node (ref "C27") (pin "2") (pinfunction "2_2") (pintype "passive"))
      (node (ref "C28") (pin "2") (pinfunction "2_2") (pintype "passive"))
      (node (ref "C29") (pin "1") (pinfunction "1_1") (pintype "passive"))
      (node (ref "C3") (pin "1") (pinfunction "1_1") (pintype "passive"))
      (node (ref "C30") (pin "1") (pinfunction "1_1") (pintype "passive"))
      (node (ref "C31") (pin "2") (pinfunction "2_2") (pintype "passive"))
      (node (ref "C32") (pin "2") (pinfunction "2_2") (pintype "passive"))
      (node (ref "C33") (pin "2") (pinfunction "2_2") (pintype "passive"))
      (node (ref "C34") (pin "2") (pinfunction "2_2") (pintype "passive"))
      (node (ref "C35") (pin "2") (pinfunction "2_2") (pintype "passive"))
      (node (ref "C36") (pin "2") (pinfunction "2_2") (pintype "passive"))
      (node (ref "C37") (pin "2") (pinfunction "2_2") (pintype "passive"))
      (node (ref "C38") (pin "2") (pinfunction "2_2") (pintype "passive"))
      (node (ref "C39") (pin "2") (pinfunction "2_2") (pintype "passive"))
      (node (ref "C4") (pin "1") (pinfunction "1_1") (pintype "passive"))
      (node (ref "C40") (pin "1") (pinfunction "1_1") (pintype "passive"))
      (node (ref "C41") (pin "2") (pinfunction "2_2") (pintype "passive"))
      (node (ref "C42") (pin "2") (pinfunction "2_2") (pintype "passive"))
      (node (ref "C5") (pin "2") (pinfunction "2_2") (pintype "passive"))
      (node (ref "C6") (pin "2") (pinfunction "2_2") (pintype "passive"))
      (node (ref "C7") (pin "1") (pinfunction "1_1") (pintype "passive"))
      (node (ref "C8") (pin "1") (pinfunction "1_1") (pintype "passive"))
      (node (ref "C9") (pin "2") (pinfunction "2_2") (pintype "passive"))
      (node (ref "J1") (pin "15") (pinfunction "DGND_15") (pintype "passive"))
      (node (ref "J2") (pin "10") (pinfunction "GND_10") (pintype "passive"))
      (node (ref "J2") (pin "6") (pinfunction "VSS_6") (pintype "passive"))
      (node (ref "J2") (pin "9") (pinfunction "K_9") (pintype "passive"))
      (node (ref "LED2") (pin "2") (pinfunction "K_2") (pintype "passive"))
      (node (ref "P1") (pin "2") (pinfunction "LEDK_2") (pintype "passive"))
      (node (ref "P1") (pin "21") (pinfunction "GND_21") (pintype "passive"))
      (node (ref "P1") (pin "22") (pinfunction "GND_22") (pintype "passive"))
      (node (ref "Q3") (pin "2") (pinfunction "E_2") (pintype "passive"))
      (node (ref "R1") (pin "2") (pinfunction "2_2") (pintype "passive"))
      (node (ref "R21") (pin "2") (pinfunction "2_2") (pintype "passive"))
      (node (ref "R24") (pin "1") (pinfunction "1_1") (pintype "passive"))
      (node (ref "R25") (pin "2") (pinfunction "2_2") (pintype "passive"))
      (node (ref "R27") (pin "2") (pinfunction "2_2") (pintype "passive"))
      (node (ref "R8") (pin "1") (pinfunction "1_1") (pintype "passive"))
      (node (ref "RST1") (pin "1") (pinfunction "1_1") (pintype "passive"))
      (node (ref "U1") (pin "C10") (pinfunction "VSS_C10") (pintype "power_in"))
      (node (ref "U1") (pin "C3") (pinfunction "VSS_C3") (pintype "power_in"))
      (node (ref "U1") (pin "C4") (pinfunction "VSS_C4") (pintype "power_in"))
      (node (ref "U1") (pin "C6") (pinfunction "VSS_C6") (pintype "power_in"))
      (node (ref "U1") (pin "C9") (pinfunction "VSS_C9") (pintype "power_in"))
      (node (ref "U1") (pin "D5") (pinfunction "VSS_D5") (pintype "power_in"))
      (node (ref "U1") (pin "D7") (pinfunction "VSS_D7") (pintype "power_in"))
      (node (ref "U1") (pin "D8") (pinfunction "VSS_D8") (pintype "power_in"))
      (node (ref "U1") (pin "E10") (pinfunction "VSS_E10") (pintype "power_in"))
      (node (ref "U1") (pin "E3") (pinfunction "VSS_E3") (pintype "power_in"))
      (node (ref "U1") (pin "E4") (pinfunction "VSS_E4") (pintype "power_in"))
      (node (ref "U1") (pin "E5") (pinfunction "VSS_E5") (pintype "power_in"))
      (node (ref "U1") (pin "E6") (pinfunction "VSS_E6") (pintype "power_in"))
      (node (ref "U1") (pin "E8") (pinfunction "VSS_E8") (pintype "power_in"))
      (node (ref "U1") (pin "F10") (pinfunction "VSS_F10") (pintype "power_in"))
      (node (ref "U1") (pin "F5") (pinfunction "VSS_F5") (pintype "power_in"))
      (node (ref "U1") (pin "F7") (pinfunction "VSS_F7") (pintype "power_in"))
      (node (ref "U1") (pin "F8") (pinfunction "VSS_F8") (pintype "power_in"))
      (node (ref "U1") (pin "F9") (pinfunction "VSS_F9") (pintype "power_in"))
      (node (ref "U1") (pin "G3") (pinfunction "VSS_G3") (pintype "power_in"))
      (node (ref "U1") (pin "G4") (pinfunction "VSS_G4") (pintype "power_in"))
      (node (ref "U1") (pin "G5") (pinfunction "VSS_G5") (pintype "power_in"))
      (node (ref "U1") (pin "G6") (pinfunction "VSS_G6") (pintype "power_in"))
      (node (ref "U1") (pin "G8") (pinfunction "VSS_G8") (pintype "power_in"))
      (node (ref "U1") (pin "H2") (pinfunction "VSS_H2") (pintype "power_in"))
      (node (ref "U1") (pin "H5") (pinfunction "VSS_H5") (pintype "power_in"))
      (node (ref "U1") (pin "H7") (pinfunction "VSS_H7") (pintype "power_in"))
      (node (ref "U1") (pin "H8") (pinfunction "VSS_H8") (pintype "power_in"))
      (node (ref "U1") (pin "H9") (pinfunction "VSS_H9") (pintype "power_in"))
      (node (ref "U1") (pin "J10") (pinfunction "VSS_J10") (pintype "power_in"))
      (node (ref "U1") (pin "J2") (pinfunction "VSS_J2") (pintype "power_in"))
      (node (ref "U1") (pin "J4") (pinfunction "VSS_J4") (pintype "power_in"))
      (node (ref "U1") (pin "J6") (pinfunction "VSS_J6") (pintype "power_in"))
      (node (ref "U1") (pin "J8") (pinfunction "VSS_J8") (pintype "power_in"))
      (node (ref "U1") (pin "K10") (pinfunction "VSS_K10") (pintype "power_in"))
      (node (ref "U1") (pin "K2") (pinfunction "VSS_K2") (pintype "power_in"))
      (node (ref "U1") (pin "K3") (pinfunction "VSS_K3") (pintype "power_in"))
      (node (ref "U1") (pin "K4") (pinfunction "VSSPLL_K4") (pintype "power_in"))
      (node (ref "U1") (pin "K5") (pinfunction "VSS_K5") (pintype "power_in"))
      (node (ref "U1") (pin "K7") (pinfunction "VSS_K7") (pintype "power_in"))
      (node (ref "U1") (pin "K9") (pinfunction "VSS_K9") (pintype "power_in"))
      (node (ref "U1") (pin "L2") (pinfunction "VSS_L2") (pintype "power_in"))
      (node (ref "U2") (pin "1") (pinfunction "GND_1") (pintype "passive"))
      (node (ref "U3") (pin "1") (pinfunction "GND_1") (pintype "passive"))
      (node (ref "U4") (pin "1") (pinfunction "GND_1") (pintype "passive"))
      (node (ref "U5") (pin "2") (pinfunction "GND_2") (pintype "power_in"))
      (node (ref "U5") (pin "25") (pinfunction "GND_25") (pintype "power_in"))
      (node (ref "U6") (pin "1") (pinfunction "GND3_1") (pintype "passive"))
      (node (ref "U6") (pin "12") (pinfunction "GND1_12") (pintype "passive"))
      (node (ref "U6") (pin "13") (pinfunction "AGND_13") (pintype "passive"))
      (node (ref "U6") (pin "15") (pinfunction "AGND_15") (pintype "passive"))
      (node (ref "U6") (pin "17") (pinfunction "AGND_17") (pintype "passive"))
      (node (ref "U6") (pin "21") (pinfunction "PAD_21") (pintype "passive"))
      (node (ref "U6") (pin "4") (pinfunction "AGND_4") (pintype "passive"))
      (node (ref "U6") (pin "5") (pinfunction "GND2_5") (pintype "passive"))
      (node (ref "U7") (pin "4") (pinfunction "GND_4") (pintype "passive"))
      (node (ref "USB1") (pin "A1") (pinfunction "GND_A1") (pintype "passive"))
      (node (ref "USB1") (pin "A12") (pinfunction "GND_A12") (pintype "passive"))
      (node (ref "USB1") (pin "B1") (pinfunction "GND_B1") (pintype "passive"))
      (node (ref "USB1") (pin "B12") (pinfunction "GND_B12") (pintype "passive"))
      (node (ref "X1") (pin "2") (pinfunction "2_2") (pintype "passive"))
      (node (ref "X1") (pin "4") (pinfunction "4_4") (pintype "passive"))
    )
    (net (code "56") (name "Net-(D1-A)") (class "Default")
      (node (ref "D1") (pin "1") (pinfunction "A_1") (pintype "passive"))
      (node (ref "LS1") (pin "2") (pinfunction "2_2") (pintype "passive"))
      (node (ref "Q3") (pin "3") (pinfunction "C_3") (pintype "passive"))
    )
    (net (code "57") (name "Net-(D1-K)") (class "Default")
      (node (ref "C18") (pin "2") (pinfunction "2_2") (pintype "passive"))
      (node (ref "D1") (pin "2") (pinfunction "K_2") (pintype "passive"))
      (node (ref "LS1") (pin "1") (pinfunction "1_1") (pintype "passive"))
      (node (ref "R19") (pin "2") (pinfunction "2_2") (pintype "passive"))
    )
    (net (code "58") (name "Net-(J1-Y0)") (class "Default")
      (node (ref "J1") (pin "24") (pinfunction "Y0_24") (pintype "passive"))
      (node (ref "R1") (pin "1") (pinfunction "1_1") (pintype "passive"))
    )
    (net (code "59") (name "Net-(J1-Y1)") (class "Default")
      (node (ref "J1") (pin "23") (pinfunction "Y1_23") (pintype "passive"))
      (node (ref "R2") (pin "1") (pinfunction "1_1") (pintype "passive"))
    )
    (net (code "60") (name "Net-(LED1-A)") (class "Default")
      (node (ref "LED1") (pin "1") (pinfunction "A_1") (pintype "passive"))
      (node (ref "R3") (pin "2") (pinfunction "2_2") (pintype "passive"))
    )
    (net (code "61") (name "Net-(LED2-A)") (class "Default")
      (node (ref "LED2") (pin "1") (pinfunction "A_1") (pintype "passive"))
      (node (ref "R9") (pin "2") (pinfunction "2_2") (pintype "passive"))
    )
    (net (code "62") (name "Net-(P1-LEDA)") (class "Default")
      (node (ref "P1") (pin "1") (pinfunction "LEDA_1") (pintype "passive"))
      (node (ref "R18") (pin "2") (pinfunction "2_2") (pintype "passive"))
    )
    (net (code "63") (name "Net-(Q1-B)") (class "Default")
      (node (ref "Q1") (pin "1") (pinfunction "B_1") (pintype "passive"))
      (node (ref "R11") (pin "2") (pinfunction "2_2") (pintype "passive"))
    )
    (net (code "64") (name "Net-(Q2-B)") (class "Default")
      (node (ref "Q2") (pin "1") (pinfunction "B_1") (pintype "passive"))
      (node (ref "R12") (pin "2") (pinfunction "2_2") (pintype "passive"))
    )
    (net (code "65") (name "Net-(Q3-B)") (class "Default")
      (node (ref "Q3") (pin "1") (pinfunction "B_1") (pintype "passive"))
      (node (ref "R22") (pin "2") (pinfunction "2_2") (pintype "passive"))
      (node (ref "R24") (pin "2") (pinfunction "2_2") (pintype "passive"))
    )
    (net (code "66") (name "Net-(U1B-CLK)") (class "Default")
      (node (ref "U1") (pin "L3") (pinfunction "OSC_CLK_L3") (pintype "passive"))
      (node (ref "U1") (pin "M2") (pinfunction "CLK_M2") (pintype "passive"))
    )
    (net (code "67") (name "Net-(U1B-XTAL_IN)") (class "Default")
      (node (ref "C13") (pin "1") (pinfunction "1_1") (pintype "passive"))
      (node (ref "R13") (pin "1") (pinfunction "1_1") (pintype "passive"))
      (node (ref "U1") (pin "M4") (pinfunction "XTAL_IN_M4") (pintype "passive"))
      (node (ref "X1") (pin "1") (pinfunction "1_1") (pintype "passive"))
    )
    (net (code "68") (name "Net-(U1B-XTAL_OUT)") (class "Default")
      (node (ref "C11") (pin "1") (pinfunction "1_1") (pintype "passive"))
      (node (ref "R13") (pin "2") (pinfunction "2_2") (pintype "passive"))
      (node (ref "U1") (pin "M3") (pinfunction "XTAL_OUT_M3") (pintype "passive"))
      (node (ref "X1") (pin "3") (pinfunction "3_3") (pintype "passive"))
    )
    (net (code "69") (name "Net-(U5-VDD)") (class "Default")
      (node (ref "C6") (pin "1") (pinfunction "1_1") (pintype "passive"))
      (node (ref "R5") (pin "2") (pinfunction "2_2") (pintype "passive"))
      (node (ref "U5") (pin "5") (pinfunction "VIO_5") (pintype "passive"))
      (node (ref "U5") (pin "6") (pinfunction "VDD_6") (pintype "passive"))
    )
    (net (code "70") (name "Net-(U5-~{RS}T)") (class "Default")
      (node (ref "R5") (pin "1") (pinfunction "1_1") (pintype "passive"))
      (node (ref "U5") (pin "9") (pinfunction "~{RS}T_9") (pintype "passive"))
    )
    (net (code "71") (name "Net-(U6-FB1)") (class "Default")
      (node (ref "R20") (pin "1") (pinfunction "1_1") (pintype "passive"))
      (node (ref "R21") (pin "1") (pinfunction "1_1") (pintype "passive"))
      (node (ref "U6") (pin "14") (pinfunction "FB1_14") (pintype "passive"))
    )
    (net (code "72") (name "Net-(U6-FB2)") (class "Default")
      (node (ref "R23") (pin "1") (pinfunction "1_1") (pintype "passive"))
      (node (ref "R25") (pin "1") (pinfunction "1_1") (pintype "passive"))
      (node (ref "U6") (pin "3") (pinfunction "FB2_3") (pintype "passive"))
    )
    (net (code "73") (name "Net-(U6-FB3)") (class "Default")
      (node (ref "R26") (pin "1") (pinfunction "1_1") (pintype "passive"))
      (node (ref "R27") (pin "1") (pinfunction "1_1") (pintype "passive"))
      (node (ref "U6") (pin "2") (pinfunction "FB3_2") (pintype "passive"))
    )
    (net (code "74") (name "Net-(U6-SW1)") (class "Default")
      (node (ref "L1") (pin "1") (pinfunction "1_1") (pintype "passive"))
      (node (ref "U6") (pin "11") (pinfunction "SW1_11") (pintype "passive"))
    )
    (net (code "75") (name "Net-(U6-SW2)") (class "Default")
      (node (ref "L2") (pin "1") (pinfunction "1_1") (pintype "passive"))
      (node (ref "U6") (pin "6") (pinfunction "SW2_6") (pintype "passive"))
    )
    (net (code "76") (name "Net-(U6-SW3)") (class "Default")
      (node (ref "L3") (pin "1") (pinfunction "1_1") (pintype "passive"))
      (node (ref "U6") (pin "20") (pinfunction "SW3_20") (pintype "passive"))
    )
    (net (code "77") (name "VBUS") (class "Default")
      (node (ref "F1") (pin "1") (pinfunction "1_1") (pintype "passive"))
      (node (ref "USB1") (pin "A4") (pinfunction "VBUS_A4") (pintype "passive"))
      (node (ref "USB1") (pin "A9") (pinfunction "VBUS_A9") (pintype "passive"))
      (node (ref "USB1") (pin "B4") (pinfunction "VBUS_B4") (pintype "passive"))
      (node (ref "USB1") (pin "B9") (pinfunction "VBUS_B9") (pintype "passive"))
    )
    (net (code "78") (name "VCC_BANK") (class "Default")
      (node (ref "C24") (pin "2") (pinfunction "2_2") (pintype "passive"))
      (node (ref "C5") (pin "1") (pinfunction "1_1") (pintype "passive"))
      (node (ref "J1") (pin "11") (pinfunction "DOVDD_11") (pintype "passive"))
      (node (ref "P1") (pin "15") (pinfunction "RD_15") (pintype "passive"))
      (node (ref "R28") (pin "1") (pinfunction "1_1") (pintype "passive"))
      (node (ref "R29") (pin "2") (pinfunction "2_2") (pintype "passive"))
      (node (ref "R4") (pin "2") (pinfunction "2_2") (pintype "passive"))
      (node (ref "R6") (pin "2") (pinfunction "2_2") (pintype "passive"))
      (node (ref "U1") (pin "D3") (pinfunction "VDDIO6C_D3") (pintype "power_in"))
      (node (ref "U1") (pin "F3") (pinfunction "VDDIO7C_F3") (pintype "power_in"))
    )
    (net (code "79") (name "VIN") (class "Default")
      (node (ref "C19") (pin "1") (pinfunction "1_1") (pintype "passive"))
      (node (ref "C22") (pin "1") (pinfunction "1_1") (pintype "passive"))
      (node (ref "C23") (pin "1") (pinfunction "1_1") (pintype "passive"))
      (node (ref "C7") (pin "2") (pinfunction "2_2") (pintype "passive"))
      (node (ref "C8") (pin "2") (pinfunction "2_2") (pintype "passive"))
      (node (ref "F1") (pin "2") (pinfunction "2_2") (pintype "passive"))
      (node (ref "R19") (pin "1") (pinfunction "1_1") (pintype "passive"))
      (node (ref "R9") (pin "1") (pinfunction "1_1") (pintype "passive"))
      (node (ref "U2") (pin "3") (pinfunction "VIN_3") (pintype "passive"))
      (node (ref "U3") (pin "3") (pinfunction "VIN_3") (pintype "passive"))
      (node (ref "U5") (pin "7") (pinfunction "REGIN_7") (pintype "passive"))
      (node (ref "U5") (pin "8") (pinfunction "VBUS_8") (pintype "power_in"))
      (node (ref "U6") (pin "10") (pinfunction "VIN1_10") (pintype "passive"))
      (node (ref "U6") (pin "16") (pinfunction "VCC_16") (pintype "passive"))
      (node (ref "U6") (pin "18") (pinfunction "EN3_18") (pintype "passive"))
      (node (ref "U6") (pin "19") (pinfunction "VIN3_19") (pintype "passive"))
      (node (ref "U6") (pin "7") (pinfunction "VIN2_7") (pintype "passive"))
      (node (ref "U6") (pin "8") (pinfunction "EN2_8") (pintype "passive"))
      (node (ref "U6") (pin "9") (pinfunction "EN1_9") (pintype "passive"))
    )
    (net (code "80") (name "unconnected-(J1-PadP0)") (class "Default")
      (node (ref "J1") (pin "P0") (pinfunction "P0_P0") (pintype "passive+no_connect"))
    )
    (net (code "81") (name "unconnected-(J1-STROBE-Pad1)") (class "Default")
      (node (ref "J1") (pin "1") (pinfunction "STROBE_1") (pintype "passive+no_connect"))
    )
    (net (code "82") (name "unconnected-(J2-DATA1-Pad8)") (class "Default")
      (node (ref "J2") (pin "8") (pinfunction "DATA1_8") (pintype "passive+no_connect"))
    )
    (net (code "83") (name "unconnected-(J2-DATA2-Pad1)") (class "Default")
      (node (ref "J2") (pin "1") (pinfunction "DATA2_1") (pintype "passive+no_connect"))
    )
    (net (code "84") (name "unconnected-(LS1-Pad3)") (class "Default")
      (node (ref "LS1") (pin "3") (pinfunction "3_3") (pintype "passive+no_connect"))
    )
    (net (code "85") (name "unconnected-(P1-NC-Pad3)") (class "Default")
      (node (ref "P1") (pin "3") (pinfunction "NC_3") (pintype "passive"))
    )
    (net (code "86") (name "unconnected-(P1-NC-Pad4)") (class "Default")
      (node (ref "P1") (pin "4") (pinfunction "NC_4") (pintype "passive"))
    )
    (net (code "87") (name "unconnected-(P1-NC-Pad5)") (class "Default")
      (node (ref "P1") (pin "5") (pinfunction "NC_5") (pintype "passive+no_connect"))
    )
    (net (code "88") (name "unconnected-(P1-TE-Pad19)") (class "Default")
      (node (ref "P1") (pin "19") (pinfunction "TE_19") (pintype "passive"))
    )
    (net (code "89") (name "unconnected-(U1A-IO_0-PadK11)") (class "Default")
      (node (ref "U1") (pin "K11") (pinfunction "IO_0_K11") (pintype "passive+no_connect"))
    )
    (net (code "90") (name "unconnected-(U1A-IO_1-PadK12)") (class "Default")
      (node (ref "U1") (pin "K12") (pinfunction "IO_1_K12") (pintype "passive+no_connect"))
    )
    (net (code "91") (name "unconnected-(U1A-IO_2-PadJ11)") (class "Default")
      (node (ref "U1") (pin "J11") (pinfunction "IO_2_J11") (pintype "passive+no_connect"))
    )
    (net (code "92") (name "unconnected-(U1A-IO_3-PadJ12)") (class "Default")
      (node (ref "U1") (pin "J12") (pinfunction "IO_3_J12") (pintype "passive+no_connect"))
    )
    (net (code "93") (name "unconnected-(U1A-IO_6-PadG11)") (class "Default")
      (node (ref "U1") (pin "G11") (pinfunction "IO_6_G11") (pintype "passive+no_connect"))
    )
    (net (code "94") (name "unconnected-(U1A-IO_7-PadG12)") (class "Default")
      (node (ref "U1") (pin "G12") (pinfunction "IO_7_G12") (pintype "passive+no_connect"))
    )
    (net (code "95") (name "unconnected-(U1A-IO_8-PadF11)") (class "Default")
      (node (ref "U1") (pin "F11") (pinfunction "IO_8_F11") (pintype "passive+no_connect"))
    )
    (net (code "96") (name "unconnected-(U1A-IO_10-PadE11)") (class "Default")
      (node (ref "U1") (pin "E11") (pinfunction "IO_10_E11") (pintype "passive+no_connect"))
    )
    (net (code "97") (name "unconnected-(U1A-IO_11-PadE12)") (class "Default")
      (node (ref "U1") (pin "E12") (pinfunction "IO_11_E12") (pintype "passive+no_connect"))
    )
    (net (code "98") (name "unconnected-(U1A-IO_12-PadD11)") (class "Default")
      (node (ref "U1") (pin "D11") (pinfunction "IO_12_D11") (pintype "passive+no_connect"))
    )
    (net (code "99") (name "unconnected-(U1A-IO_13-PadD12)") (class "Default")
      (node (ref "U1") (pin "D12") (pinfunction "IO_13_D12") (pintype "passive+no_connect"))
    )
    (net (code "100") (name "unconnected-(U1A-IO_14-PadC11)") (class "Default")
      (node (ref "U1") (pin "C11") (pinfunction "IO_14_C11") (pintype "passive+no_connect"))
    )
    (net (code "101") (name "unconnected-(U1A-IO_15-PadC12)") (class "Default")
      (node (ref "U1") (pin "C12") (pinfunction "IO_15_C12") (pintype "passive+no_connect"))
    )
    (net (code "102") (name "unconnected-(U1A-IO_17-PadA12)") (class "Default")
      (node (ref "U1") (pin "A12") (pinfunction "IO_17_A12") (pintype "passive+no_connect"))
    )
    (net (code "103") (name "unconnected-(U1A-IO_18-PadB11)") (class "Default")
      (node (ref "U1") (pin "B11") (pinfunction "IO_18_B11") (pintype "passive+no_connect"))
    )
    (net (code "104") (name "unconnected-(U1A-IO_19-PadA11)") (class "Default")
      (node (ref "U1") (pin "A11") (pinfunction "IO_19_A11") (pintype "passive+no_connect"))
    )
    (net (code "105") (name "unconnected-(U1A-IO_20-PadB10)") (class "Default")
      (node (ref "U1") (pin "B10") (pinfunction "IO_20_B10") (pintype "passive+no_connect"))
    )
    (net (code "106") (name "unconnected-(U1A-IO_21-PadA10)") (class "Default")
      (node (ref "U1") (pin "A10") (pinfunction "IO_21_A10") (pintype "passive+no_connect"))
    )
    (net (code "107") (name "unconnected-(U1A-IO_22-PadB9)") (class "Default")
      (node (ref "U1") (pin "B9") (pinfunction "IO_22_B9") (pintype "passive+no_connect"))
    )
    (net (code "108") (name "unconnected-(U1A-IO_23-PadA9)") (class "Default")
      (node (ref "U1") (pin "A9") (pinfunction "IO_23_A9") (pintype "passive+no_connect"))
    )
    (net (code "109") (name "unconnected-(U1A-IO_24-PadB8)") (class "Default")
      (node (ref "U1") (pin "B8") (pinfunction "IO_24_B8") (pintype "passive+no_connect"))
    )
    (net (code "110") (name "unconnected-(U1A-IO_25-PadA8)") (class "Default")
      (node (ref "U1") (pin "A8") (pinfunction "IO_25_A8") (pintype "passive+no_connect"))
    )
    (net (code "111") (name "unconnected-(U1A-IO_30-PadB5)") (class "Default")
      (node (ref "U1") (pin "B5") (pinfunction "IO_30_B5") (pintype "passive+no_connect"))
    )
    (net (code "112") (name "unconnected-(U1A-IO_31-PadA5)") (class "Default")
      (node (ref "U1") (pin "A5") (pinfunction "IO_31_A5") (pintype "passive+no_connect"))
    )
    (net (code "113") (name "unconnected-(U1A-IO_32-PadB4)") (class "Default")
      (node (ref "U1") (pin "B4") (pinfunction "IO_32_B4") (pintype "passive+no_connect"))
    )
    (net (code "114") (name "unconnected-(U1A-IO_33-PadA4)") (class "Default")
      (node (ref "U1") (pin "A4") (pinfunction "IO_33_A4") (pintype "passive+no_connect"))
    )
    (net (code "115") (name "unconnected-(U1A-IO_34-PadB3)") (class "Default")
      (node (ref "U1") (pin "B3") (pinfunction "IO_34_B3") (pintype "passive+no_connect"))
    )
    (net (code "116") (name "unconnected-(U5-CTS-Pad18)") (class "Default")
      (node (ref "U5") (pin "18") (pinfunction "CTS_18") (pintype "passive+no_connect"))
    )
    (net (code "117") (name "unconnected-(U5-DCD-Pad24)") (class "Default")
      (node (ref "U5") (pin "24") (pinfunction "DCD_24") (pintype "passive+no_connect"))
    )
    (net (code "118") (name "unconnected-(U5-DSR-Pad22)") (class "Default")
      (node (ref "U5") (pin "22") (pinfunction "DSR_22") (pintype "passive+no_connect"))
    )
    (net (code "119") (name "unconnected-(U5-GPIO.0-Pad14)") (class "Default")
      (node (ref "U5") (pin "14") (pinfunction "GPIO.0_14") (pintype "passive+no_connect"))
    )
    (net (code "120") (name "unconnected-(U5-GPIO.1-Pad13)") (class "Default")
      (node (ref "U5") (pin "13") (pinfunction "GPIO.1_13") (pintype "passive+no_connect"))
    )
    (net (code "121") (name "unconnected-(U5-GPIO.2-Pad12)") (class "Default")
      (node (ref "U5") (pin "12") (pinfunction "GPIO.2_12") (pintype "passive+no_connect"))
    )
    (net (code "122") (name "unconnected-(U5-GPIO.3-Pad11)") (class "Default")
      (node (ref "U5") (pin "11") (pinfunction "GPIO.3_11") (pintype "passive+no_connect"))
    )
    (net (code "123") (name "unconnected-(U5-NC-Pad10)") (class "Default")
      (node (ref "U5") (pin "10") (pinfunction "NC_10") (pintype "passive+no_connect"))
    )
    (net (code "124") (name "unconnected-(U5-RI-Pad1)") (class "Default")
      (node (ref "U5") (pin "1") (pinfunction "RI_1") (pintype "passive+no_connect"))
    )
    (net (code "125") (name "unconnected-(U5-SUSPEND-Pad17)") (class "Default")
      (node (ref "U5") (pin "17") (pinfunction "SUSPEND_17") (pintype "passive+no_connect"))
    )
    (net (code "126") (name "unconnected-(U5-VPP-Pad16)") (class "Default")
      (node (ref "U5") (pin "16") (pinfunction "VPP_16") (pintype "passive+no_connect"))
    )
    (net (code "127") (name "unconnected-(U5-~{SUSPEND}-Pad15)") (class "Default")
      (node (ref "U5") (pin "15") (pinfunction "~{SUSPEND}_15") (pintype "passive+no_connect"))
    )
    (net (code "128") (name "unconnected-(USB1-CC1-PadA5)") (class "Default")
      (node (ref "USB1") (pin "A5") (pinfunction "CC1_A5") (pintype "passive"))
    )
    (net (code "129") (name "unconnected-(USB1-CC2-PadB5)") (class "Default")
      (node (ref "USB1") (pin "B5") (pinfunction "CC2_B5") (pintype "passive+no_connect"))
    )
    (net (code "130") (name "unconnected-(USB1-RX1+-PadB11)") (class "Default")
      (node (ref "USB1") (pin "B11") (pinfunction "RX1+_B11") (pintype "passive+no_connect"))
    )
    (net (code "131") (name "unconnected-(USB1-RX1--PadB10)") (class "Default")
      (node (ref "USB1") (pin "B10") (pinfunction "RX1-_B10") (pintype "passive+no_connect"))
    )
    (net (code "132") (name "unconnected-(USB1-RX2+-PadA11)") (class "Default")
      (node (ref "USB1") (pin "A11") (pinfunction "RX2+_A11") (pintype "passive+no_connect"))
    )
    (net (code "133") (name "unconnected-(USB1-RX2--PadA10)") (class "Default")
      (node (ref "USB1") (pin "A10") (pinfunction "RX2-_A10") (pintype "passive+no_connect"))
    )
    (net (code "134") (name "unconnected-(USB1-SBU1-PadA8)") (class "Default")
      (node (ref "USB1") (pin "A8") (pinfunction "SBU1_A8") (pintype "passive+no_connect"))
    )
    (net (code "135") (name "unconnected-(USB1-SBU2-PadB8)") (class "Default")
      (node (ref "USB1") (pin "B8") (pinfunction "SBU2_B8") (pintype "passive+no_connect"))
    )
    (net (code "136") (name "unconnected-(USB1-SH1-Pad1)") (class "Default")
      (node (ref "USB1") (pin "1") (pinfunction "SH1_1") (pintype "passive"))
    )
    (net (code "137") (name "unconnected-(USB1-SH2-Pad2)") (class "Default")
      (node (ref "USB1") (pin "2") (pinfunction "SH2_2") (pintype "passive"))
    )
    (net (code "138") (name "unconnected-(USB1-SH3-Pad3)") (class "Default")
      (node (ref "USB1") (pin "3") (pinfunction "SH3_3") (pintype "passive"))
    )
    (net (code "139") (name "unconnected-(USB1-SH4-Pad4)") (class "Default")
      (node (ref "USB1") (pin "4") (pinfunction "SH4_4") (pintype "passive"))
    )
    (net (code "140") (name "unconnected-(USB1-TX1+-PadA2)") (class "Default")
      (node (ref "USB1") (pin "A2") (pinfunction "TX1+_A2") (pintype "passive+no_connect"))
    )
    (net (code "141") (name "unconnected-(USB1-TX1--PadA3)") (class "Default")
      (node (ref "USB1") (pin "A3") (pinfunction "TX1-_A3") (pintype "passive+no_connect"))
    )
    (net (code "142") (name "unconnected-(USB1-TX2+-PadB2)") (class "Default")
      (node (ref "USB1") (pin "B2") (pinfunction "TX2+_B2") (pintype "passive+no_connect"))
    )
    (net (code "143") (name "unconnected-(USB1-TX2--PadB3)") (class "Default")
      (node (ref "USB1") (pin "B3") (pinfunction "TX2-_B3") (pintype "passive+no_connect"))
    )
  )
)
